# audio-adapter.net
KiCad netlist of a schematic drawn in EAGLE
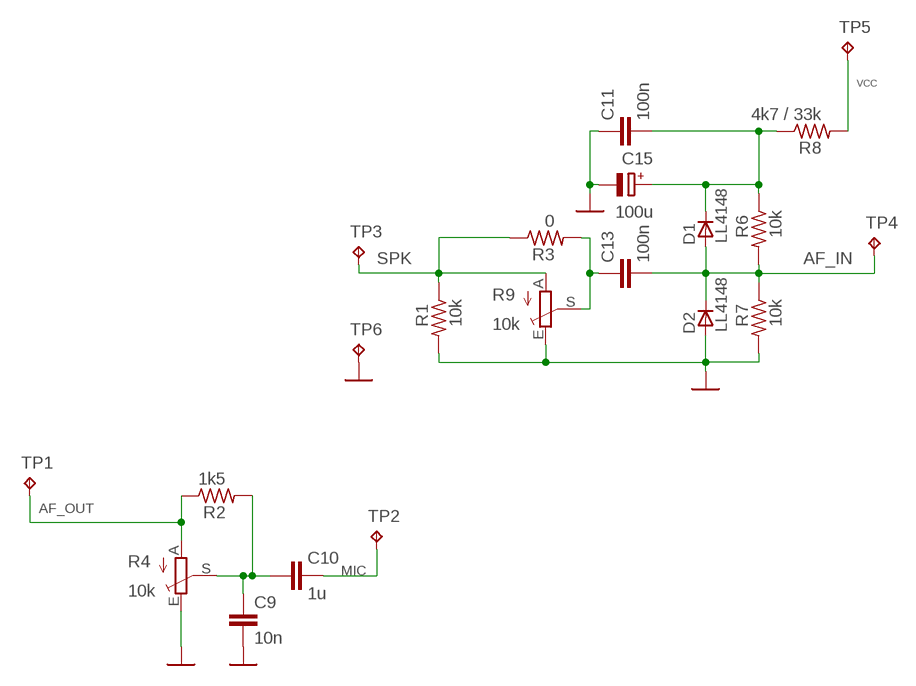
[diagram p0: schematic, sheet 1]

(export (version "E")
  (design (tool "Eeschema 10.0.6"))
  (components
    (comp (ref "C9")
      (value "10n")
      (footprint "eagle-import:C0805")
      (libsource (lib "eagle-import") (part "C-EUC0805"))
    )
    (comp (ref "C10")
      (value "1u")
      (footprint "eagle-import:C0805")
      (libsource (lib "eagle-import") (part "C-EUC0805"))
    )
    (comp (ref "C11")
      (value "100n")
      (footprint "eagle-import:C0805")
      (libsource (lib "eagle-import") (part "C-EUC0805"))
    )
    (comp (ref "C13")
      (value "100n")
      (footprint "eagle-import:C0805")
      (libsource (lib "eagle-import") (part "C-EUC0805"))
    )
    (comp (ref "C15")
      (value "100u")
      (footprint "eagle-import:SMC_D")
      (libsource (lib "eagle-import") (part "CPOL-EUSMCD"))
    )
    (comp (ref "D1")
      (value "LL4148")
      (footprint "eagle-import:SOD80_DO213AA_MINIMELF")
      (libsource (lib "eagle-import") (part "LL4148"))
    )
    (comp (ref "D2")
      (value "LL4148")
      (footprint "eagle-import:SOD80_DO213AA_MINIMELF")
      (libsource (lib "eagle-import") (part "LL4148"))
    )
    (comp (ref "R1")
      (value "10k")
      (footprint "eagle-import:R0805")
      (libsource (lib "eagle-import") (part "R-US_R0805"))
    )
    (comp (ref "R2")
      (value "1k5")
      (footprint "eagle-import:R0805")
      (libsource (lib "eagle-import") (part "R-US_R0805"))
    )
    (comp (ref "R3")
      (value "0")
      (footprint "eagle-import:R0805")
      (libsource (lib "eagle-import") (part "R-US_R0805"))
    )
    (comp (ref "R4")
      (value "10k")
      (footprint "eagle-import:CA6H")
      (libsource (lib "eagle-import") (part "TRIM_EU-CA6H"))
    )
    (comp (ref "R6")
      (value "10k")
      (footprint "eagle-import:R0805")
      (libsource (lib "eagle-import") (part "R-US_R0805"))
    )
    (comp (ref "R7")
      (value "10k")
      (footprint "eagle-import:R0805")
      (libsource (lib "eagle-import") (part "R-US_R0805"))
    )
    (comp (ref "R8")
      (value "4k7 / 33k")
      (footprint "eagle-import:R0805")
      (libsource (lib "eagle-import") (part "R-US_R0805"))
    )
    (comp (ref "R9")
      (value "10k")
      (footprint "eagle-import:CA6H")
      (libsource (lib "eagle-import") (part "TRIM_EU-CA6H"))
    )
    (comp (ref "TP1")
      (value "TPB1,27")
      (footprint "eagle-import:B1,27")
      (libsource (lib "eagle-import") (part "TPB1,27"))
    )
    (comp (ref "TP2")
      (value "TPB1,27")
      (footprint "eagle-import:B1,27")
      (libsource (lib "eagle-import") (part "TPB1,27"))
    )
    (comp (ref "TP3")
      (value "TPB1,27")
      (footprint "eagle-import:B1,27")
      (libsource (lib "eagle-import") (part "TPB1,27"))
    )
    (comp (ref "TP4")
      (value "TPB1,27")
      (footprint "eagle-import:B1,27")
      (libsource (lib "eagle-import") (part "TPB1,27"))
    )
    (comp (ref "TP5")
      (value "TPB1,27")
      (footprint "eagle-import:B1,27")
      (libsource (lib "eagle-import") (part "TPB1,27"))
    )
    (comp (ref "TP6")
      (value "TPB1,27")
      (footprint "eagle-import:B1,27")
      (libsource (lib "eagle-import") (part "TPB1,27"))
    )
  )
  (nets
    (net (code "1") (name "/AF_IN") (class "Default")
      (node (ref "C13") (pin "2") (pinfunction "2_2") (pintype "passive"))
      (node (ref "D1") (pin "A") (pinfunction "A_A") (pintype "passive"))
      (node (ref "D2") (pin "C") (pinfunction "C_C") (pintype "passive"))
      (node (ref "R6") (pin "2") (pinfunction "2_2") (pintype "passive"))
      (node (ref "R7") (pin "1") (pinfunction "1_1") (pintype "passive"))
      (node (ref "TP4") (pin "TP") (pinfunction "TP_TP") (pintype "input"))
    )
    (net (code "2") (name "/AF_OUT") (class "Default")
      (node (ref "R2") (pin "1") (pinfunction "1_1") (pintype "passive"))
      (node (ref "R4") (pin "A") (pinfunction "A_A") (pintype "passive"))
      (node (ref "TP1") (pin "TP") (pinfunction "TP_TP") (pintype "input"))
    )
    (net (code "3") (name "/MIC") (class "Default")
      (node (ref "C10") (pin "2") (pinfunction "2_2") (pintype "passive"))
      (node (ref "TP2") (pin "TP") (pinfunction "TP_TP") (pintype "input"))
    )
    (net (code "4") (name "/SPK") (class "Default")
      (node (ref "R1") (pin "1") (pinfunction "1_1") (pintype "passive"))
      (node (ref "R3") (pin "1") (pinfunction "1_1") (pintype "passive"))
      (node (ref "R9") (pin "A") (pinfunction "A_A") (pintype "passive"))
      (node (ref "TP3") (pin "TP") (pinfunction "TP_TP") (pintype "input"))
    )
    (net (code "5") (name "/VCC") (class "Default")
      (node (ref "R8") (pin "2") (pinfunction "2_2") (pintype "passive"))
      (node (ref "TP5") (pin "TP") (pinfunction "TP_TP") (pintype "input"))
    )
    (net (code "6") (name "GND") (class "Default")
      (node (ref "C11") (pin "1") (pinfunction "1_1") (pintype "passive"))
      (node (ref "C15") (pin "-") (pinfunction "-_-") (pintype "passive"))
      (node (ref "C9") (pin "2") (pinfunction "2_2") (pintype "passive"))
      (node (ref "D2") (pin "A") (pinfunction "A_A") (pintype "passive"))
      (node (ref "R1") (pin "2") (pinfunction "2_2") (pintype "passive"))
      (node (ref "R4") (pin "E") (pinfunction "E_E") (pintype "passive"))
      (node (ref "R7") (pin "2") (pinfunction "2_2") (pintype "passive"))
      (node (ref "R9") (pin "E") (pinfunction "E_E") (pintype "passive"))
      (node (ref "TP6") (pin "TP") (pinfunction "TP_TP") (pintype "input"))
    )
    (net (code "7") (name "Net-(C10-Pad1)") (class "Default")
      (node (ref "C10") (pin "1") (pinfunction "1_1") (pintype "passive"))
      (node (ref "C9") (pin "1") (pinfunction "1_1") (pintype "passive"))
      (node (ref "R2") (pin "2") (pinfunction "2_2") (pintype "passive"))
      (node (ref "R4") (pin "S") (pinfunction "S_S") (pintype "passive"))
    )
    (net (code "8") (name "Net-(C11-Pad2)") (class "Default")
      (node (ref "C11") (pin "2") (pinfunction "2_2") (pintype "passive"))
      (node (ref "C15") (pin "+") (pinfunction "+_+") (pintype "passive"))
      (node (ref "D1") (pin "C") (pinfunction "C_C") (pintype "passive"))
      (node (ref "R6") (pin "1") (pinfunction "1_1") (pintype "passive"))
      (node (ref "R8") (pin "1") (pinfunction "1_1") (pintype "passive"))
    )
    (net (code "9") (name "Net-(C13-Pad1)") (class "Default")
      (node (ref "C13") (pin "1") (pinfunction "1_1") (pintype "passive"))
      (node (ref "R3") (pin "2") (pinfunction "2_2") (pintype "passive"))
      (node (ref "R9") (pin "S") (pinfunction "S_S") (pintype "passive"))
    )
  )
)
